# SensorPCB.net
KiCad netlist of a schematic drawn in EasyEDA Pro
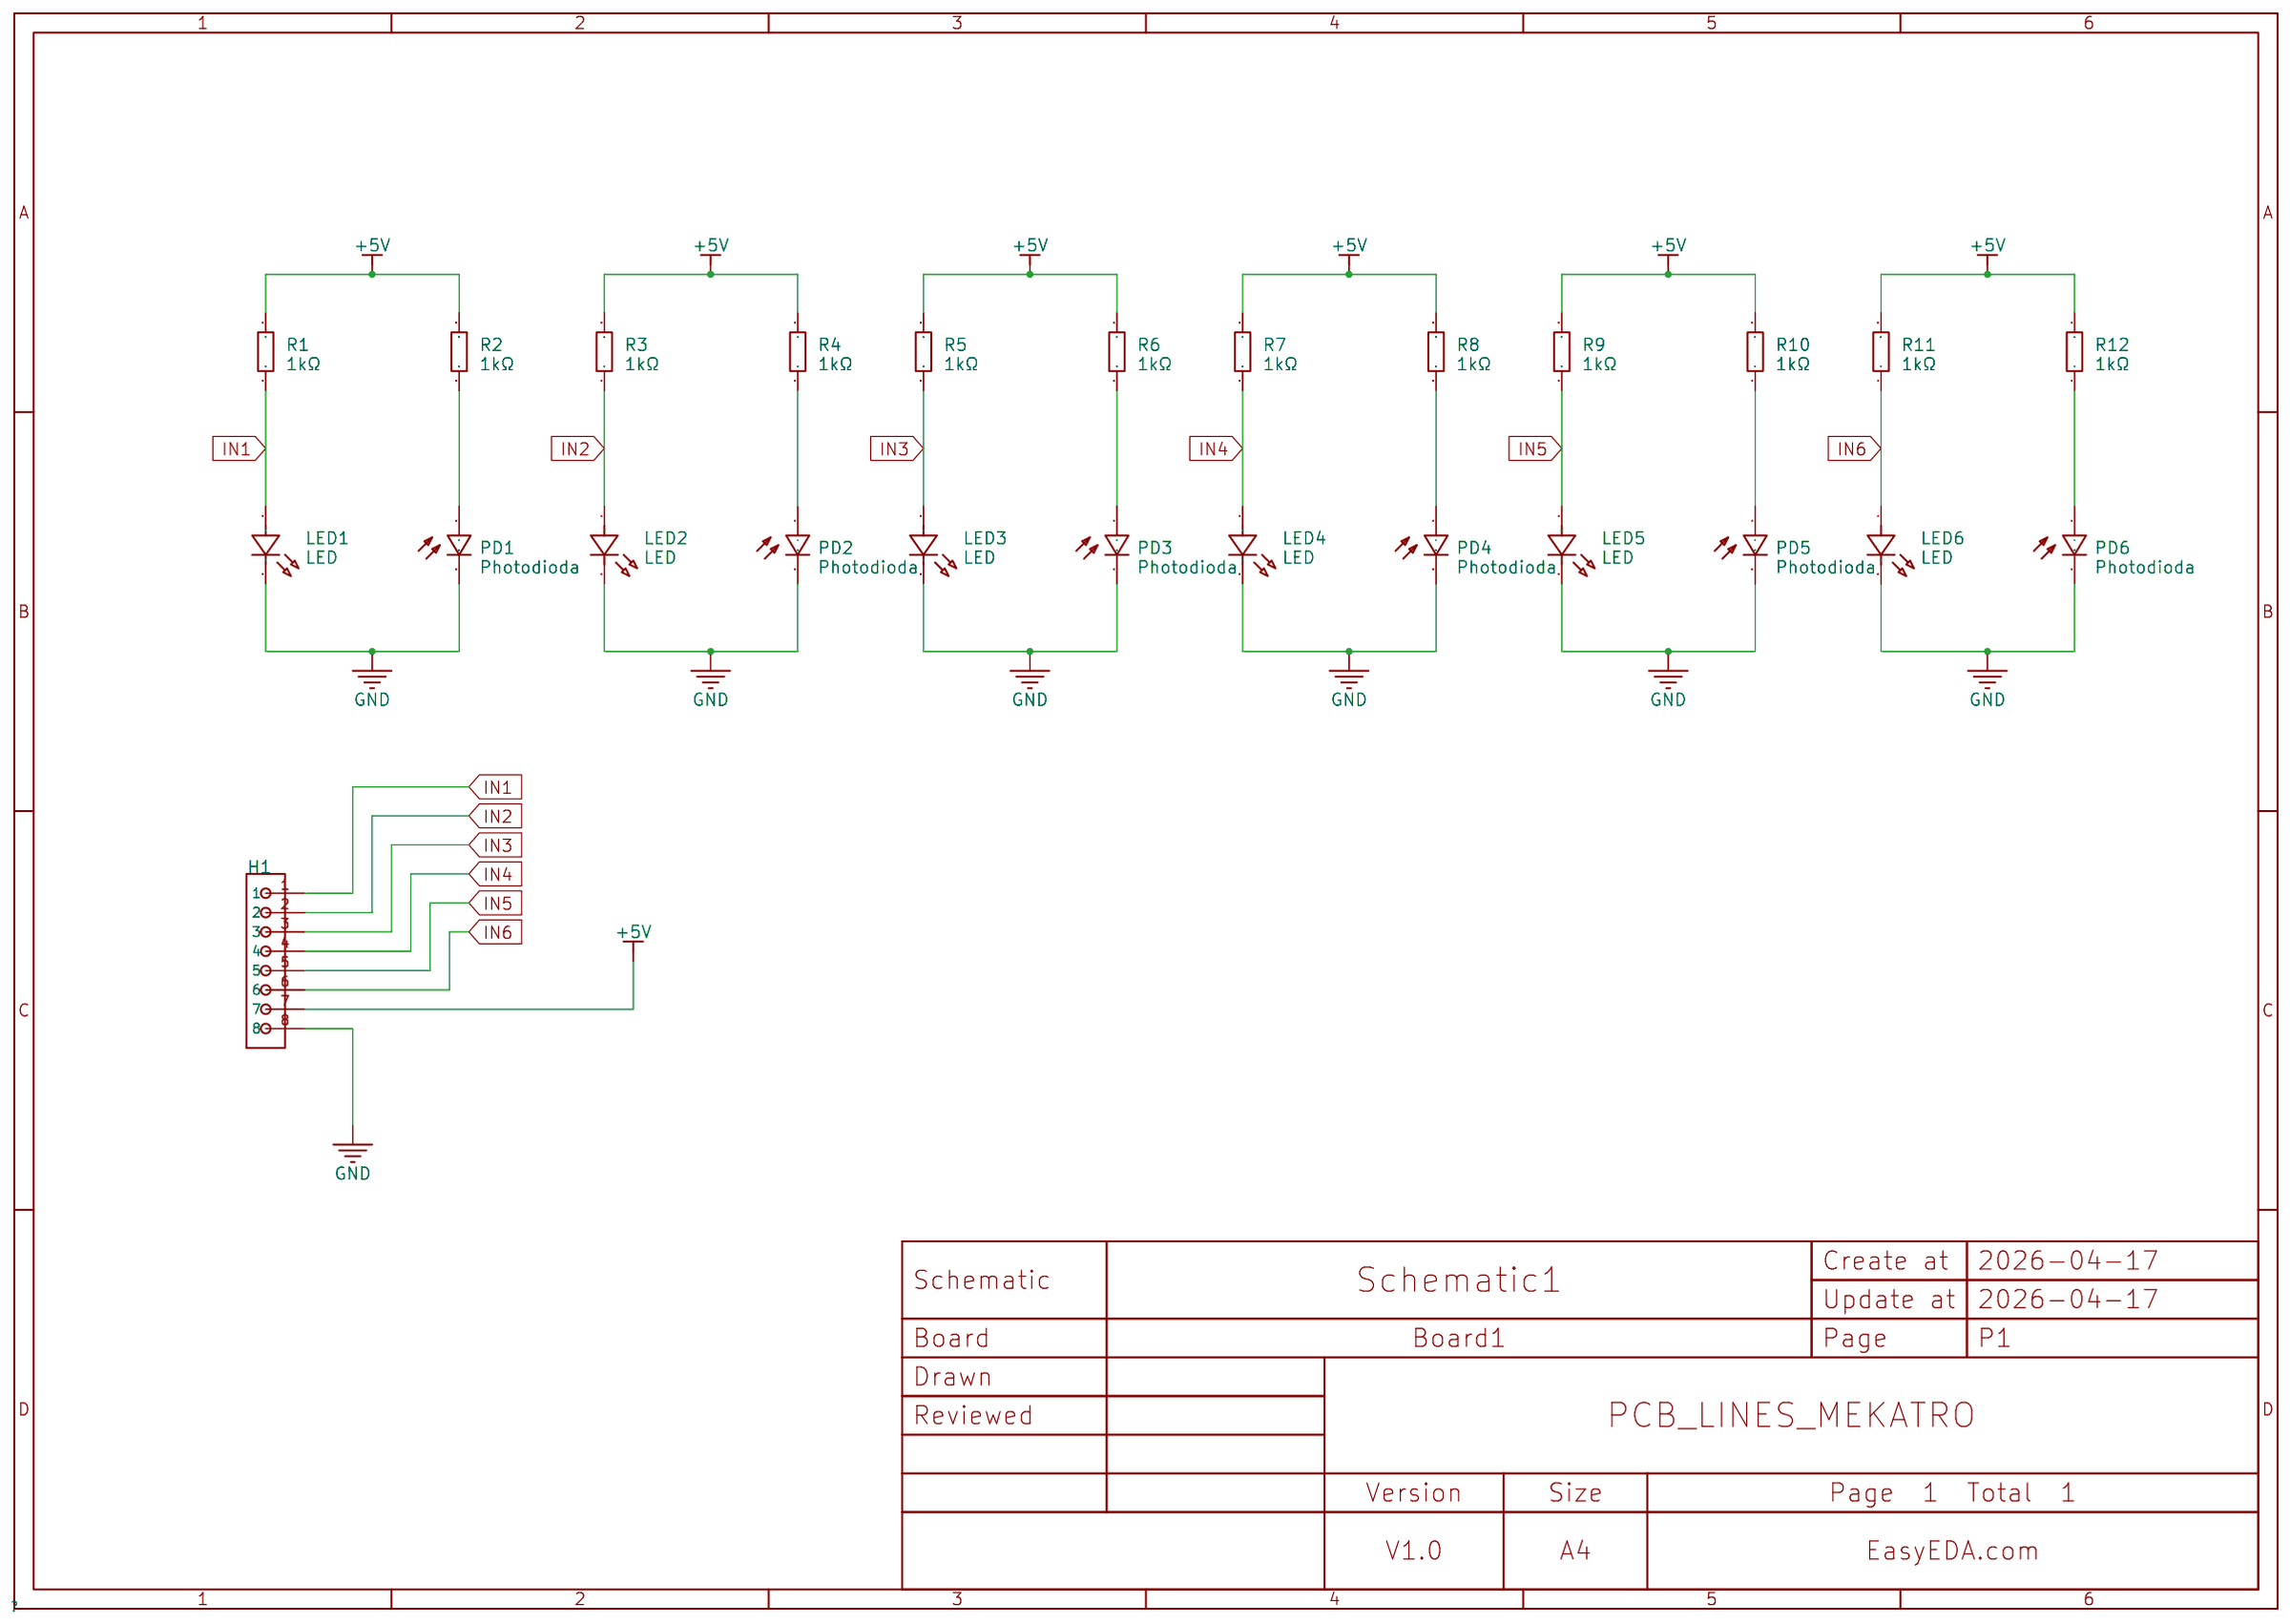
[diagram p0: schematic sheet]

(export (version "E")
  (design (tool "Eeschema 10.0.6"))
  (components
    (comp (ref "H1")
      (value "~")
      (footprint "easyedapro:PIN_HEADER_1X8_MALE")
      (libsource (lib "easyedapro") (part "pin_header_1x8_male"))
    )
    (comp (ref "LED1")
      (value "LED")
      (footprint "easyedapro:LED0603-FD")
      (libsource (lib "easyedapro") (part "940NM_SMT_LED_0603"))
    )
    (comp (ref "LED2")
      (value "LED")
      (footprint "easyedapro:LED0603-FD")
      (libsource (lib "easyedapro") (part "940NM_SMT_LED_0603"))
    )
    (comp (ref "LED3")
      (value "LED")
      (footprint "easyedapro:LED0603-FD")
      (libsource (lib "easyedapro") (part "940NM_SMT_LED_0603"))
    )
    (comp (ref "LED4")
      (value "LED")
      (footprint "easyedapro:LED0603-FD")
      (libsource (lib "easyedapro") (part "940NM_SMT_LED_0603"))
    )
    (comp (ref "LED5")
      (value "LED")
      (footprint "easyedapro:LED0603-FD")
      (libsource (lib "easyedapro") (part "940NM_SMT_LED_0603"))
    )
    (comp (ref "LED6")
      (value "LED")
      (footprint "easyedapro:LED0603-FD")
      (libsource (lib "easyedapro") (part "940NM_SMT_LED_0603"))
    )
    (comp (ref "PD1")
      (value "Photodioda")
      (footprint "easyedapro:LED-TH_BD3.5-P2.54-FD")
      (libsource (lib "easyedapro") (part "Photodioda"))
    )
    (comp (ref "PD2")
      (value "Photodioda")
      (footprint "easyedapro:LED-TH_BD3.5-P2.54-FD")
      (libsource (lib "easyedapro") (part "Photodioda"))
    )
    (comp (ref "PD3")
      (value "Photodioda")
      (footprint "easyedapro:LED-TH_BD3.5-P2.54-FD")
      (libsource (lib "easyedapro") (part "Photodioda"))
    )
    (comp (ref "PD4")
      (value "Photodioda")
      (footprint "easyedapro:LED-TH_BD3.5-P2.54-FD")
      (libsource (lib "easyedapro") (part "Photodioda"))
    )
    (comp (ref "PD5")
      (value "Photodioda")
      (footprint "easyedapro:LED-TH_BD3.5-P2.54-FD")
      (libsource (lib "easyedapro") (part "Photodioda"))
    )
    (comp (ref "PD6")
      (value "Photodioda")
      (footprint "easyedapro:LED-TH_BD3.5-P2.54-FD")
      (libsource (lib "easyedapro") (part "Photodioda"))
    )
    (comp (ref "R1")
      (value "1kΩ")
      (footprint "easyedapro:R0805")
      (fields
        (field (name "Manufacturer Part") "0805W8F1001T5E")
        (field (name "Manufacturer") "UNI-ROYAL(厚声)")
      )
      (libsource (lib "easyedapro") (part "0805W8F1001T5E"))
    )
    (comp (ref "R2")
      (value "1kΩ")
      (footprint "easyedapro:R0805")
      (fields
        (field (name "Manufacturer Part") "0805W8F1001T5E")
        (field (name "Manufacturer") "UNI-ROYAL(厚声)")
      )
      (libsource (lib "easyedapro") (part "0805W8F1001T5E"))
    )
    (comp (ref "R3")
      (value "1kΩ")
      (footprint "easyedapro:R0805")
      (fields
        (field (name "Manufacturer Part") "0805W8F1001T5E")
        (field (name "Manufacturer") "UNI-ROYAL(厚声)")
      )
      (libsource (lib "easyedapro") (part "0805W8F1001T5E"))
    )
    (comp (ref "R4")
      (value "1kΩ")
      (footprint "easyedapro:R0805")
      (fields
        (field (name "Manufacturer Part") "0805W8F1001T5E")
        (field (name "Manufacturer") "UNI-ROYAL(厚声)")
      )
      (libsource (lib "easyedapro") (part "0805W8F1001T5E"))
    )
    (comp (ref "R5")
      (value "1kΩ")
      (footprint "easyedapro:R0805")
      (fields
        (field (name "Manufacturer Part") "0805W8F1001T5E")
        (field (name "Manufacturer") "UNI-ROYAL(厚声)")
      )
      (libsource (lib "easyedapro") (part "0805W8F1001T5E"))
    )
    (comp (ref "R6")
      (value "1kΩ")
      (footprint "easyedapro:R0805")
      (fields
        (field (name "Manufacturer Part") "0805W8F1001T5E")
        (field (name "Manufacturer") "UNI-ROYAL(厚声)")
      )
      (libsource (lib "easyedapro") (part "0805W8F1001T5E"))
    )
    (comp (ref "R7")
      (value "1kΩ")
      (footprint "easyedapro:R0805")
      (fields
        (field (name "Manufacturer Part") "0805W8F1001T5E")
        (field (name "Manufacturer") "UNI-ROYAL(厚声)")
      )
      (libsource (lib "easyedapro") (part "0805W8F1001T5E"))
    )
    (comp (ref "R8")
      (value "1kΩ")
      (footprint "easyedapro:R0805")
      (fields
        (field (name "Manufacturer Part") "0805W8F1001T5E")
        (field (name "Manufacturer") "UNI-ROYAL(厚声)")
      )
      (libsource (lib "easyedapro") (part "0805W8F1001T5E"))
    )
    (comp (ref "R9")
      (value "1kΩ")
      (footprint "easyedapro:R0805")
      (fields
        (field (name "Manufacturer Part") "0805W8F1001T5E")
        (field (name "Manufacturer") "UNI-ROYAL(厚声)")
      )
      (libsource (lib "easyedapro") (part "0805W8F1001T5E"))
    )
    (comp (ref "R10")
      (value "1kΩ")
      (footprint "easyedapro:R0805")
      (fields
        (field (name "Manufacturer Part") "0805W8F1001T5E")
        (field (name "Manufacturer") "UNI-ROYAL(厚声)")
      )
      (libsource (lib "easyedapro") (part "0805W8F1001T5E"))
    )
    (comp (ref "R11")
      (value "1kΩ")
      (footprint "easyedapro:R0805")
      (fields
        (field (name "Manufacturer Part") "0805W8F1001T5E")
        (field (name "Manufacturer") "UNI-ROYAL(厚声)")
      )
      (libsource (lib "easyedapro") (part "0805W8F1001T5E"))
    )
    (comp (ref "R12")
      (value "1kΩ")
      (footprint "easyedapro:R0805")
      (fields
        (field (name "Manufacturer Part") "0805W8F1001T5E")
        (field (name "Manufacturer") "UNI-ROYAL(厚声)")
      )
      (libsource (lib "easyedapro") (part "0805W8F1001T5E"))
    )
  )
  (nets
    (net (code "1") (name "+5V") (class "Default")
      (node (ref "H1") (pin "7") (pinfunction "7_7") (pintype "input"))
      (node (ref "R1") (pin "2") (pinfunction "2_2") (pintype "input"))
      (node (ref "R10") (pin "2") (pinfunction "2_2") (pintype "input"))
      (node (ref "R11") (pin "2") (pinfunction "2_2") (pintype "input"))
      (node (ref "R12") (pin "2") (pinfunction "2_2") (pintype "input"))
      (node (ref "R2") (pin "2") (pinfunction "2_2") (pintype "input"))
      (node (ref "R3") (pin "2") (pinfunction "2_2") (pintype "input"))
      (node (ref "R4") (pin "2") (pinfunction "2_2") (pintype "input"))
      (node (ref "R5") (pin "2") (pinfunction "2_2") (pintype "input"))
      (node (ref "R6") (pin "2") (pinfunction "2_2") (pintype "input"))
      (node (ref "R7") (pin "2") (pinfunction "2_2") (pintype "input"))
      (node (ref "R8") (pin "2") (pinfunction "2_2") (pintype "input"))
      (node (ref "R9") (pin "2") (pinfunction "2_2") (pintype "input"))
    )
    (net (code "2") (name "GND") (class "Default")
      (node (ref "H1") (pin "8") (pinfunction "8_8") (pintype "input"))
      (node (ref "LED1") (pin "2") (pinfunction "K_2") (pintype "unspecified"))
      (node (ref "LED2") (pin "2") (pinfunction "K_2") (pintype "unspecified"))
      (node (ref "LED3") (pin "2") (pinfunction "K_2") (pintype "unspecified"))
      (node (ref "LED4") (pin "2") (pinfunction "K_2") (pintype "unspecified"))
      (node (ref "LED5") (pin "2") (pinfunction "K_2") (pintype "unspecified"))
      (node (ref "LED6") (pin "2") (pinfunction "K_2") (pintype "unspecified"))
      (node (ref "PD1") (pin "2") (pinfunction "C_2") (pintype "input"))
      (node (ref "PD2") (pin "2") (pinfunction "C_2") (pintype "input"))
      (node (ref "PD3") (pin "2") (pinfunction "C_2") (pintype "input"))
      (node (ref "PD4") (pin "2") (pinfunction "C_2") (pintype "input"))
      (node (ref "PD5") (pin "2") (pinfunction "C_2") (pintype "input"))
      (node (ref "PD6") (pin "2") (pinfunction "C_2") (pintype "input"))
    )
    (net (code "3") (name "IN1") (class "Default")
      (node (ref "H1") (pin "1") (pinfunction "1_1") (pintype "input"))
      (node (ref "LED1") (pin "1") (pinfunction "A_1") (pintype "unspecified"))
      (node (ref "R1") (pin "1") (pinfunction "1_1") (pintype "input"))
    )
    (net (code "4") (name "IN2") (class "Default")
      (node (ref "H1") (pin "2") (pinfunction "2_2") (pintype "input"))
      (node (ref "LED2") (pin "1") (pinfunction "A_1") (pintype "unspecified"))
      (node (ref "R3") (pin "1") (pinfunction "1_1") (pintype "input"))
    )
    (net (code "5") (name "IN3") (class "Default")
      (node (ref "H1") (pin "3") (pinfunction "3_3") (pintype "input"))
      (node (ref "LED3") (pin "1") (pinfunction "A_1") (pintype "unspecified"))
      (node (ref "R5") (pin "1") (pinfunction "1_1") (pintype "input"))
    )
    (net (code "6") (name "IN4") (class "Default")
      (node (ref "H1") (pin "4") (pinfunction "4_4") (pintype "input"))
      (node (ref "LED4") (pin "1") (pinfunction "A_1") (pintype "unspecified"))
      (node (ref "R7") (pin "1") (pinfunction "1_1") (pintype "input"))
    )
    (net (code "7") (name "IN5") (class "Default")
      (node (ref "H1") (pin "5") (pinfunction "5_5") (pintype "input"))
      (node (ref "LED5") (pin "1") (pinfunction "A_1") (pintype "unspecified"))
      (node (ref "R9") (pin "1") (pinfunction "1_1") (pintype "input"))
    )
    (net (code "8") (name "IN6") (class "Default")
      (node (ref "H1") (pin "6") (pinfunction "6_6") (pintype "input"))
      (node (ref "LED6") (pin "1") (pinfunction "A_1") (pintype "unspecified"))
      (node (ref "R11") (pin "1") (pinfunction "1_1") (pintype "input"))
    )
    (net (code "9") (name "Net-(PD1-A)") (class "Default")
      (node (ref "PD1") (pin "1") (pinfunction "A_1") (pintype "input"))
      (node (ref "R2") (pin "1") (pinfunction "1_1") (pintype "input"))
    )
    (net (code "10") (name "Net-(PD2-A)") (class "Default")
      (node (ref "PD2") (pin "1") (pinfunction "A_1") (pintype "input"))
      (node (ref "R4") (pin "1") (pinfunction "1_1") (pintype "input"))
    )
    (net (code "11") (name "Net-(PD3-A)") (class "Default")
      (node (ref "PD3") (pin "1") (pinfunction "A_1") (pintype "input"))
      (node (ref "R6") (pin "1") (pinfunction "1_1") (pintype "input"))
    )
    (net (code "12") (name "Net-(PD4-A)") (class "Default")
      (node (ref "PD4") (pin "1") (pinfunction "A_1") (pintype "input"))
      (node (ref "R8") (pin "1") (pinfunction "1_1") (pintype "input"))
    )
    (net (code "13") (name "Net-(PD5-A)") (class "Default")
      (node (ref "PD5") (pin "1") (pinfunction "A_1") (pintype "input"))
      (node (ref "R10") (pin "1") (pinfunction "1_1") (pintype "input"))
    )
    (net (code "14") (name "Net-(PD6-A)") (class "Default")
      (node (ref "PD6") (pin "1") (pinfunction "A_1") (pintype "input"))
      (node (ref "R12") (pin "1") (pinfunction "1_1") (pintype "input"))
    )
  )
)
